# Main_Shield.net
KiCad netlist of a schematic drawn in EAGLE
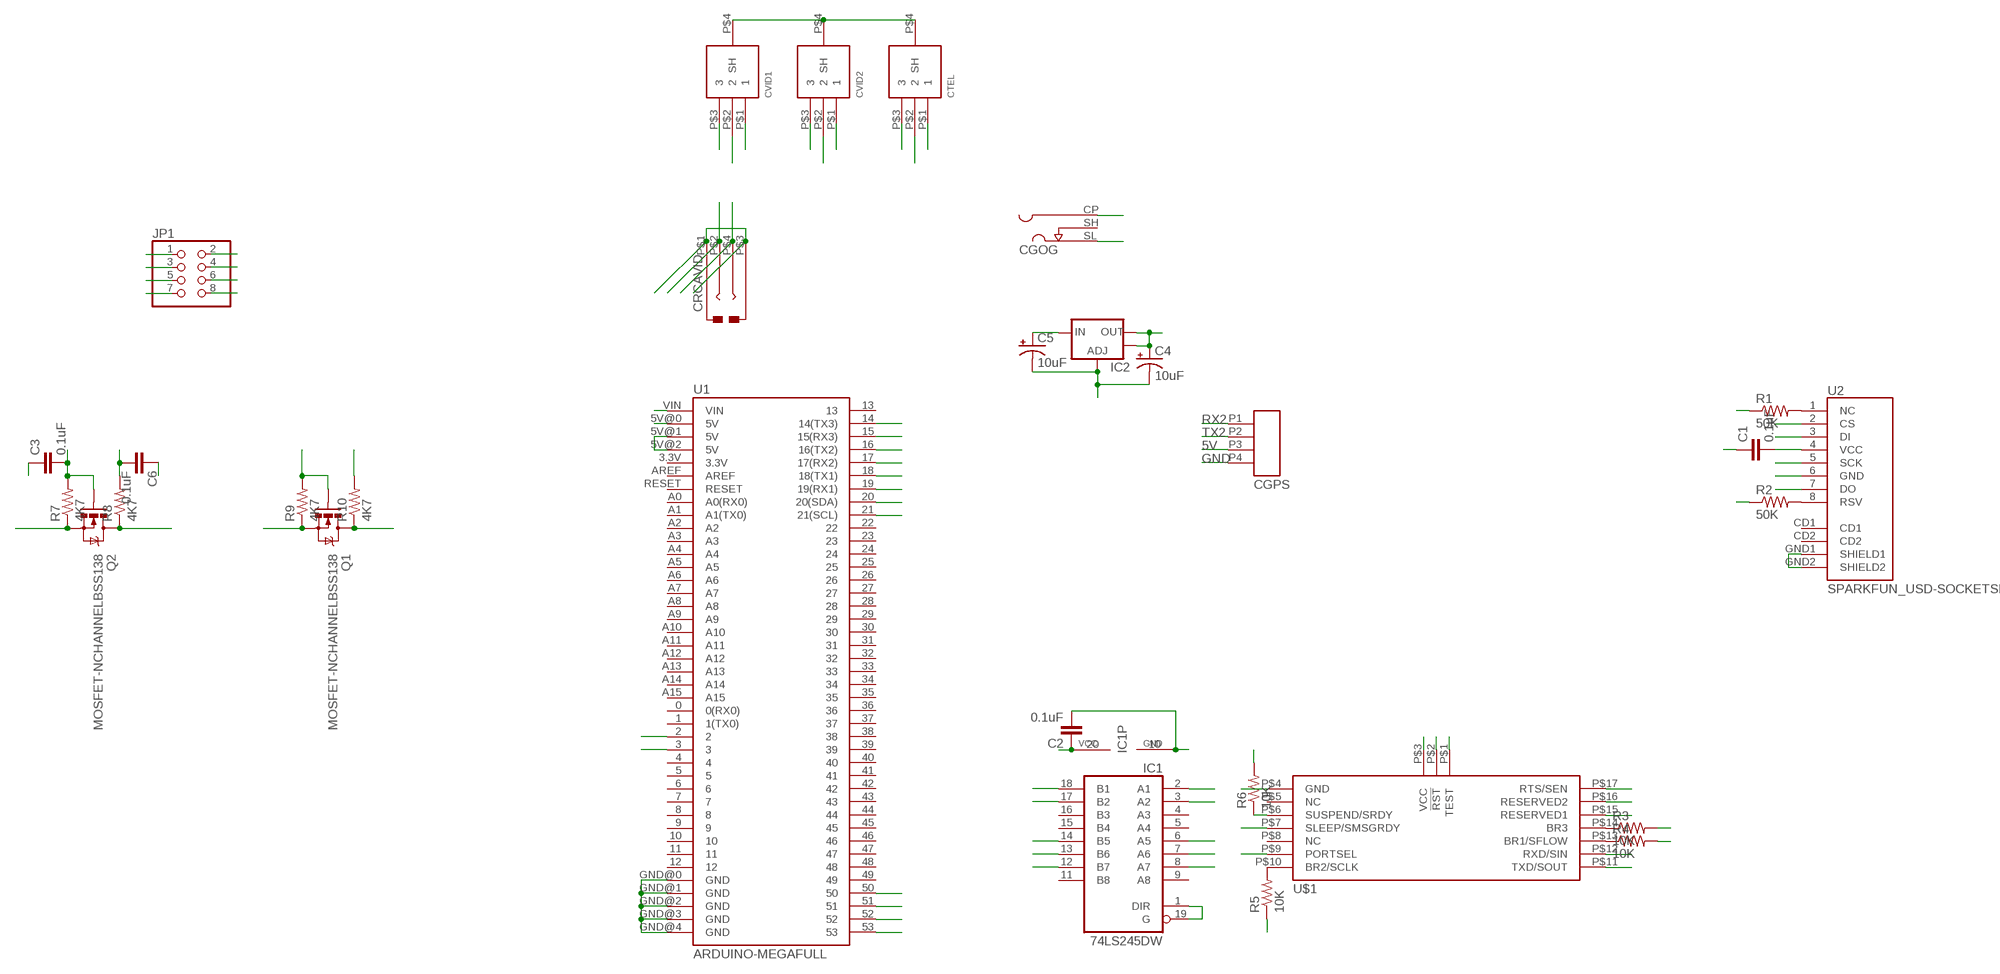
[diagram p0: schematic, sheet 1]

(export (version "E")
  (design (tool "Eeschema 10.0.6"))
  (components
    (comp (ref "C1")
      (value "0.1uF")
      (footprint "eagle-import:0603-CAP")
      (libsource (lib "eagle-import") (part "0.1UF-25V(+80/-20%)(0603)"))
    )
    (comp (ref "C2")
      (value "0.1uF")
      (footprint "eagle-import:0603-CAP")
      (fields (field (name "PROD_ID") "CAP-00810"))
      (libsource (lib "eagle-import") (part "0.1UF-25V(+80/-20%)(0603)"))
    )
    (comp (ref "C3")
      (value "0.1uF")
      (footprint "eagle-import:0603-CAP")
      (fields (field (name "PROD_ID") "CAP-00810"))
      (libsource (lib "eagle-import") (part "0.1UF-25V(+80/-20%)(0603)"))
    )
    (comp (ref "C4")
      (value "10uF")
      (footprint "eagle-import:EIA3216")
      (libsource (lib "eagle-import") (part "10UF-TANT"))
    )
    (comp (ref "C5")
      (value "10uF")
      (footprint "eagle-import:EIA3216")
      (fields (field (name "PROD_ID") "CAP-00811"))
      (libsource (lib "eagle-import") (part "10UF-TANT"))
    )
    (comp (ref "C6")
      (value "0.1uF")
      (footprint "eagle-import:0603-CAP")
      (fields (field (name "PROD_ID") "CAP-00810"))
      (libsource (lib "eagle-import") (part "0.1UF-25V(+80/-20%)(0603)"))
    )
    (comp (ref "CGOG")
      (value "L722RAS")
      (footprint "eagle-import:L722RAS")
      (libsource (lib "eagle-import") (part "L722RAS"))
    )
    (comp (ref "CGPS")
      (value "TRAPC4MSX")
      (footprint "eagle-import:TRAPC4MSX")
      (libsource (lib "eagle-import") (part "TRAPC4MSX"))
    )
    (comp (ref "CRCAVID")
      (value "RCJ-2123")
      (footprint "eagle-import:RCJ-2123")
      (libsource (lib "eagle-import") (part "RCJ-2123"))
    )
    (comp (ref "CTEL")
      (value "TRA3M")
      (footprint "eagle-import:TRA3M")
      (libsource (lib "eagle-import") (part "TRA3M"))
    )
    (comp (ref "CVID1")
      (value "TRA3M")
      (footprint "eagle-import:TRA3M")
      (libsource (lib "eagle-import") (part "TRA3M"))
    )
    (comp (ref "CVID2")
      (value "TRA3M")
      (footprint "eagle-import:TRA3M")
      (libsource (lib "eagle-import") (part "TRA3M"))
    )
    (comp (ref "IC1")
      (value "74LS245DW")
      (footprint "eagle-import:SO20W")
      (libsource (lib "eagle-import") (part "74245DWLS"))
    )
    (comp (ref "IC2")
      (value "V_REG_LM1117SOT223")
      (footprint "eagle-import:SOT223")
      (libsource (lib "eagle-import") (part "V_REG_LM1117SOT223"))
    )
    (comp (ref "JP1")
      (value "PINHD-2X04_MICROMATCH")
      (footprint "eagle-import:MICROMATCH-8")
      (libsource (lib "eagle-import") (part "PINHD-2X04_MICROMATCH"))
    )
    (comp (ref "Q1")
      (value "MOSFET-NCHANNELBSS138")
      (footprint "eagle-import:SOT23")
      (libsource (lib "eagle-import") (part "MOSFET-NCHANNELBSS138"))
    )
    (comp (ref "Q2")
      (value "MOSFET-NCHANNELBSS138")
      (footprint "eagle-import:SOT23")
      (libsource (lib "eagle-import") (part "MOSFET-NCHANNELBSS138"))
    )
    (comp (ref "R1")
      (value "50K")
      (footprint "eagle-import:0603-RES")
      (libsource (lib "eagle-import") (part "RESISTOR0603-RES"))
    )
    (comp (ref "R2")
      (value "50K")
      (footprint "eagle-import:0603-RES")
      (libsource (lib "eagle-import") (part "RESISTOR0603-RES"))
    )
    (comp (ref "R3")
      (value "10K")
      (footprint "eagle-import:0603-RES")
      (libsource (lib "eagle-import") (part "RESISTOR0603-RES"))
    )
    (comp (ref "R4")
      (value "10K")
      (footprint "eagle-import:0603-RES")
      (libsource (lib "eagle-import") (part "RESISTOR0603-RES"))
    )
    (comp (ref "R5")
      (value "10K")
      (footprint "eagle-import:0603-RES")
      (libsource (lib "eagle-import") (part "RESISTOR0603-RES"))
    )
    (comp (ref "R6")
      (value "10K")
      (footprint "eagle-import:0603-RES")
      (libsource (lib "eagle-import") (part "RESISTOR0603-RES"))
    )
    (comp (ref "R7")
      (value "4K7")
      (footprint "eagle-import:0603-RES")
      (libsource (lib "eagle-import") (part "RESISTOR0603-RES"))
    )
    (comp (ref "R8")
      (value "4K7")
      (footprint "eagle-import:0603-RES")
      (libsource (lib "eagle-import") (part "RESISTOR0603-RES"))
    )
    (comp (ref "R9")
      (value "4K7")
      (footprint "eagle-import:0603-RES")
      (libsource (lib "eagle-import") (part "RESISTOR0603-RES"))
    )
    (comp (ref "R10")
      (value "4K7")
      (footprint "eagle-import:0603-RES")
      (libsource (lib "eagle-import") (part "RESISTOR0603-RES"))
    )
    (comp (ref "U$1")
      (value "ANTAP281MXIB")
      (footprint "eagle-import:ANTAP281MXIB")
      (libsource (lib "eagle-import") (part "ANTAP281MXIB"))
    )
    (comp (ref "U1")
      (value "ARDUINO-MEGAFULL")
      (footprint "eagle-import:ARDUINO_MEGA")
      (libsource (lib "eagle-import") (part "ARDUINO-MEGAFULL"))
    )
    (comp (ref "U2")
      (value "SPARKFUN_USD-SOCKETSMD")
      (footprint "eagle-import:SPARKFUN_MICRO-SD-SOCKET-PP")
      (libsource (lib "eagle-import") (part "SPARKFUN_USD-SOCKETSMD"))
    )
  )
  (nets
    (net (code "1") (name "/3V3") (class "Default")
      (node (ref "C1") (pin "2") (pinfunction "2_2") (pintype "passive"))
      (node (ref "C2") (pin "1") (pinfunction "1_1") (pintype "passive"))
      (node (ref "C3") (pin "2") (pinfunction "2_2") (pintype "passive"))
      (node (ref "C4") (pin "A") (pinfunction "+_A") (pintype "passive"))
      (node (ref "IC1") (pin "20") (pinfunction "VCC_20") (pintype "power_in"))
      (node (ref "IC2") (pin "2") (pinfunction "OUT_2") (pintype "output"))
      (node (ref "IC2") (pin "4") (pinfunction "OUT_4") (pintype "output"))
      (node (ref "JP1") (pin "2") (pinfunction "2_2") (pintype "passive"))
      (node (ref "Q1") (pin "1") (pinfunction "G_1") (pintype "passive"))
      (node (ref "Q2") (pin "1") (pinfunction "G_1") (pintype "passive"))
      (node (ref "R1") (pin "1") (pinfunction "1_1") (pintype "passive"))
      (node (ref "R2") (pin "1") (pinfunction "1_1") (pintype "passive"))
      (node (ref "R3") (pin "2") (pinfunction "2_2") (pintype "passive"))
      (node (ref "R4") (pin "2") (pinfunction "2_2") (pintype "passive"))
      (node (ref "R5") (pin "1") (pinfunction "1_1") (pintype "passive"))
      (node (ref "R6") (pin "2") (pinfunction "2_2") (pintype "passive"))
      (node (ref "R7") (pin "2") (pinfunction "2_2") (pintype "passive"))
      (node (ref "R9") (pin "2") (pinfunction "2_2") (pintype "passive"))
      (node (ref "U$1") (pin "P$3") (pinfunction "VCC_P$3") (pintype "bidirectional"))
      (node (ref "U2") (pin "4") (pinfunction "VCC_4") (pintype "bidirectional"))
    )
    (net (code "2") (name "/5V") (class "Default")
      (node (ref "C5") (pin "A") (pinfunction "+_A") (pintype "passive"))
      (node (ref "C6") (pin "2") (pinfunction "2_2") (pintype "passive"))
      (node (ref "CGPS") (pin "P3") (pinfunction "P$3_P3") (pintype "bidirectional"))
      (node (ref "CVID1") (pin "P$1") (pinfunction "1_P$1") (pintype "bidirectional"))
      (node (ref "CVID2") (pin "P$1") (pinfunction "1_P$1") (pintype "bidirectional"))
      (node (ref "IC2") (pin "3") (pinfunction "IN_3") (pintype "input"))
      (node (ref "JP1") (pin "4") (pinfunction "4_4") (pintype "passive"))
      (node (ref "R10") (pin "2") (pinfunction "2_2") (pintype "passive"))
      (node (ref "R8") (pin "2") (pinfunction "2_2") (pintype "passive"))
      (node (ref "U1") (pin "5V@0") (pinfunction "5V_5V@0") (pintype "bidirectional"))
      (node (ref "U1") (pin "5V@1") (pinfunction "5V_5V@1") (pintype "bidirectional"))
      (node (ref "U1") (pin "5V@2") (pinfunction "5V_5V@2") (pintype "bidirectional"))
    )
    (net (code "3") (name "/CSMMC") (class "Default")
      (node (ref "IC1") (pin "8") (pinfunction "A7_8") (pintype "bidirectional"))
      (node (ref "U2") (pin "2") (pinfunction "CS_2") (pintype "bidirectional"))
    )
    (net (code "4") (name "/DIMMC") (class "Default")
      (node (ref "IC1") (pin "7") (pinfunction "A6_7") (pintype "bidirectional"))
      (node (ref "U2") (pin "3") (pinfunction "DI_3") (pintype "bidirectional"))
    )
    (net (code "5") (name "/DOMMC") (class "Default")
      (node (ref "U1") (pin "50") (pinfunction "50_50") (pintype "bidirectional"))
      (node (ref "U2") (pin "7") (pinfunction "DO_7") (pintype "bidirectional"))
    )
    (net (code "6") (name "/GND") (class "Default")
      (node (ref "C1") (pin "1") (pinfunction "1_1") (pintype "passive"))
      (node (ref "C2") (pin "2") (pinfunction "2_2") (pintype "passive"))
      (node (ref "C3") (pin "1") (pinfunction "1_1") (pintype "passive"))
      (node (ref "C4") (pin "C") (pinfunction "-_C") (pintype "passive"))
      (node (ref "C5") (pin "C") (pinfunction "-_C") (pintype "passive"))
      (node (ref "C6") (pin "1") (pinfunction "1_1") (pintype "passive"))
      (node (ref "CGOG") (pin "SL") (pinfunction "SLEEVE_SL") (pintype "bidirectional"))
      (node (ref "CGPS") (pin "P4") (pinfunction "P$4_P4") (pintype "bidirectional"))
      (node (ref "CRCAVID") (pin "P$1") (pinfunction "P$1_P$1") (pintype "bidirectional"))
      (node (ref "CRCAVID") (pin "P$3") (pinfunction "P$3_P$3") (pintype "bidirectional"))
      (node (ref "CTEL") (pin "P$3") (pinfunction "3_P$3") (pintype "bidirectional"))
      (node (ref "CTEL") (pin "P$4") (pinfunction "SH_P$4") (pintype "bidirectional"))
      (node (ref "CVID1") (pin "P$3") (pinfunction "3_P$3") (pintype "bidirectional"))
      (node (ref "CVID1") (pin "P$4") (pinfunction "SH_P$4") (pintype "bidirectional"))
      (node (ref "CVID2") (pin "P$3") (pinfunction "3_P$3") (pintype "bidirectional"))
      (node (ref "CVID2") (pin "P$4") (pinfunction "SH_P$4") (pintype "bidirectional"))
      (node (ref "IC1") (pin "1") (pinfunction "DIR_1") (pintype "input"))
      (node (ref "IC1") (pin "10") (pinfunction "GND_10") (pintype "power_in"))
      (node (ref "IC1") (pin "19") (pinfunction "G_19") (pintype "input"))
      (node (ref "IC2") (pin "1") (pinfunction "ADJ_1") (pintype "input"))
      (node (ref "JP1") (pin "1") (pinfunction "1_1") (pintype "passive"))
      (node (ref "JP1") (pin "3") (pinfunction "3_3") (pintype "passive"))
      (node (ref "U$1") (pin "P$1") (pinfunction "TEST_P$1") (pintype "bidirectional"))
      (node (ref "U$1") (pin "P$15") (pinfunction "RESERVED1_P$15") (pintype "bidirectional"))
      (node (ref "U$1") (pin "P$16") (pinfunction "RESERVED2_P$16") (pintype "bidirectional"))
      (node (ref "U$1") (pin "P$4") (pinfunction "GND_P$4") (pintype "bidirectional"))
      (node (ref "U$1") (pin "P$7") (pinfunction "SLEEP/SMSGRDY_P$7") (pintype "bidirectional"))
      (node (ref "U$1") (pin "P$9") (pinfunction "PORTSEL_P$9") (pintype "bidirectional"))
      (node (ref "U1") (pin "GND@0") (pinfunction "GND_GND@0") (pintype "bidirectional"))
      (node (ref "U1") (pin "GND@1") (pinfunction "GND_GND@1") (pintype "bidirectional"))
      (node (ref "U1") (pin "GND@2") (pinfunction "GND_GND@2") (pintype "bidirectional"))
      (node (ref "U1") (pin "GND@3") (pinfunction "GND_GND@3") (pintype "bidirectional"))
      (node (ref "U1") (pin "GND@4") (pinfunction "GND_GND@4") (pintype "bidirectional"))
      (node (ref "U2") (pin "6") (pinfunction "GND_6") (pintype "bidirectional"))
      (node (ref "U2") (pin "GND1") (pinfunction "SHIELD1_GND1") (pintype "bidirectional"))
      (node (ref "U2") (pin "GND2") (pinfunction "SHIELD2_GND2") (pintype "bidirectional"))
    )
    (net (code "7") (name "/MOSI") (class "Default")
      (node (ref "IC1") (pin "13") (pinfunction "B6_13") (pintype "bidirectional"))
      (node (ref "U1") (pin "51") (pinfunction "51_51") (pintype "bidirectional"))
    )
    (net (code "8") (name "/RTSANT") (class "Default")
      (node (ref "U$1") (pin "P$17") (pinfunction "RTS/SEN_P$17") (pintype "bidirectional"))
      (node (ref "U1") (pin "2") (pinfunction "2_2") (pintype "bidirectional"))
    )
    (net (code "9") (name "/RX2") (class "Default")
      (node (ref "CGPS") (pin "P1") (pinfunction "P$1_P1") (pintype "bidirectional"))
      (node (ref "U1") (pin "17") (pinfunction "17(RX2)_17") (pintype "bidirectional"))
    )
    (net (code "10") (name "/RXANT") (class "Default")
      (node (ref "IC1") (pin "2") (pinfunction "A1_2") (pintype "bidirectional"))
      (node (ref "U$1") (pin "P$12") (pinfunction "RXD/SIN_P$12") (pintype "bidirectional"))
    )
    (net (code "11") (name "/RXOSD") (class "Default")
      (node (ref "CTEL") (pin "P$2") (pinfunction "2_P$2") (pintype "bidirectional"))
      (node (ref "U1") (pin "14") (pinfunction "14(TX3)_14") (pintype "bidirectional"))
    )
    (net (code "12") (name "/SCK") (class "Default")
      (node (ref "IC1") (pin "14") (pinfunction "B5_14") (pintype "bidirectional"))
      (node (ref "U1") (pin "52") (pinfunction "52_52") (pintype "bidirectional"))
    )
    (net (code "13") (name "/SCKMMC") (class "Default")
      (node (ref "IC1") (pin "6") (pinfunction "A5_6") (pintype "bidirectional"))
      (node (ref "U2") (pin "5") (pinfunction "SCK_5") (pintype "bidirectional"))
    )
    (net (code "14") (name "/SCL3V3") (class "Default")
      (node (ref "JP1") (pin "7") (pinfunction "7_7") (pintype "passive"))
      (node (ref "Q1") (pin "2") (pinfunction "S_2") (pintype "passive"))
      (node (ref "R9") (pin "1") (pinfunction "1_1") (pintype "passive"))
    )
    (net (code "15") (name "/SCL5V") (class "Default")
      (node (ref "JP1") (pin "8") (pinfunction "8_8") (pintype "passive"))
      (node (ref "Q1") (pin "3") (pinfunction "D_3") (pintype "passive"))
      (node (ref "R10") (pin "1") (pinfunction "1_1") (pintype "passive"))
      (node (ref "U1") (pin "21") (pinfunction "21(SCL)_21") (pintype "bidirectional"))
    )
    (net (code "16") (name "/SDA3V3") (class "Default")
      (node (ref "JP1") (pin "5") (pinfunction "5_5") (pintype "passive"))
      (node (ref "Q2") (pin "2") (pinfunction "S_2") (pintype "passive"))
      (node (ref "R7") (pin "1") (pinfunction "1_1") (pintype "passive"))
    )
    (net (code "17") (name "/SDA5V") (class "Default")
      (node (ref "JP1") (pin "6") (pinfunction "6_6") (pintype "passive"))
      (node (ref "Q2") (pin "3") (pinfunction "D_3") (pintype "passive"))
      (node (ref "R8") (pin "1") (pinfunction "1_1") (pintype "passive"))
      (node (ref "U1") (pin "20") (pinfunction "20(SDA)_20") (pintype "bidirectional"))
    )
    (net (code "18") (name "/SS") (class "Default")
      (node (ref "IC1") (pin "12") (pinfunction "B7_12") (pintype "bidirectional"))
      (node (ref "U1") (pin "53") (pinfunction "53_53") (pintype "bidirectional"))
    )
    (net (code "19") (name "/TX1") (class "Default")
      (node (ref "IC1") (pin "18") (pinfunction "B1_18") (pintype "bidirectional"))
      (node (ref "U1") (pin "18") (pinfunction "18(TX1)_18") (pintype "bidirectional"))
    )
    (net (code "20") (name "/TX2") (class "Default")
      (node (ref "CGPS") (pin "P2") (pinfunction "P$2_P2") (pintype "bidirectional"))
      (node (ref "U1") (pin "16") (pinfunction "16(TX2)_16") (pintype "bidirectional"))
    )
    (net (code "21") (name "/TXANT") (class "Default")
      (node (ref "U$1") (pin "P$11") (pinfunction "TXD/SOUT_P$11") (pintype "bidirectional"))
      (node (ref "U1") (pin "19") (pinfunction "19(RX1)_19") (pintype "bidirectional"))
    )
    (net (code "22") (name "/TXOSD") (class "Default")
      (node (ref "CTEL") (pin "P$1") (pinfunction "1_P$1") (pintype "bidirectional"))
      (node (ref "U1") (pin "15") (pinfunction "15(RX3)_15") (pintype "bidirectional"))
    )
    (net (code "23") (name "/VBAT") (class "Default")
      (node (ref "CGOG") (pin "CP") (pinfunction "CENTRE_CP") (pintype "bidirectional"))
      (node (ref "U1") (pin "VIN") (pinfunction "VIN_VIN") (pintype "bidirectional"))
    )
    (net (code "24") (name "/VID1") (class "Default")
      (node (ref "CRCAVID") (pin "P$2") (pinfunction "P$2_P$2") (pintype "bidirectional"))
      (node (ref "CVID1") (pin "P$2") (pinfunction "2_P$2") (pintype "bidirectional"))
    )
    (net (code "25") (name "/VID2") (class "Default")
      (node (ref "CRCAVID") (pin "P$4") (pinfunction "P$4_P$4") (pintype "bidirectional"))
      (node (ref "CVID2") (pin "P$2") (pinfunction "2_P$2") (pintype "bidirectional"))
    )
    (net (code "26") (name "/~{RST}ANT") (class "Default")
      (node (ref "IC1") (pin "3") (pinfunction "A2_3") (pintype "bidirectional"))
      (node (ref "U$1") (pin "P$2") (pinfunction "~{RST}_P$2") (pintype "bidirectional"))
    )
    (net (code "27") (name "/~{RST}ANT5V") (class "Default")
      (node (ref "IC1") (pin "17") (pinfunction "B2_17") (pintype "bidirectional"))
      (node (ref "U1") (pin "3") (pinfunction "3_3") (pintype "bidirectional"))
    )
    (net (code "28") (name "Net-(U$1-BR1{slash}SFLOW)") (class "Default")
      (node (ref "R4") (pin "1") (pinfunction "1_1") (pintype "passive"))
      (node (ref "U$1") (pin "P$13") (pinfunction "BR1/SFLOW_P$13") (pintype "bidirectional"))
    )
    (net (code "29") (name "Net-(U$1-BR2{slash}SCLK)") (class "Default")
      (node (ref "R5") (pin "2") (pinfunction "2_2") (pintype "passive"))
      (node (ref "U$1") (pin "P$10") (pinfunction "BR2/SCLK_P$10") (pintype "bidirectional"))
    )
    (net (code "30") (name "Net-(U$1-BR3)") (class "Default")
      (node (ref "R3") (pin "1") (pinfunction "1_1") (pintype "passive"))
      (node (ref "U$1") (pin "P$14") (pinfunction "BR3_P$14") (pintype "bidirectional"))
    )
    (net (code "31") (name "Net-(U$1-SUSPEND{slash}SRDY)") (class "Default")
      (node (ref "R6") (pin "1") (pinfunction "1_1") (pintype "passive"))
      (node (ref "U$1") (pin "P$6") (pinfunction "SUSPEND/SRDY_P$6") (pintype "bidirectional"))
    )
    (net (code "32") (name "Net-(U2-NC)") (class "Default")
      (node (ref "R1") (pin "2") (pinfunction "2_2") (pintype "passive"))
      (node (ref "U2") (pin "1") (pinfunction "NC_1") (pintype "bidirectional"))
    )
    (net (code "33") (name "Net-(U2-RSV)") (class "Default")
      (node (ref "R2") (pin "2") (pinfunction "2_2") (pintype "passive"))
      (node (ref "U2") (pin "8") (pinfunction "RSV_8") (pintype "bidirectional"))
    )
    (net (code "34") (name "unconnected-(CGOG-SHUNT-PadSH)") (class "Default")
      (node (ref "CGOG") (pin "SH") (pinfunction "SHUNT_SH") (pintype "bidirectional"))
    )
    (net (code "35") (name "unconnected-(IC1A-A3-Pad4)") (class "Default")
      (node (ref "IC1") (pin "4") (pinfunction "A3_4") (pintype "bidirectional"))
    )
    (net (code "36") (name "unconnected-(IC1A-A4-Pad5)") (class "Default")
      (node (ref "IC1") (pin "5") (pinfunction "A4_5") (pintype "bidirectional"))
    )
    (net (code "37") (name "unconnected-(IC1A-A8-Pad9)") (class "Default")
      (node (ref "IC1") (pin "9") (pinfunction "A8_9") (pintype "bidirectional"))
    )
    (net (code "38") (name "unconnected-(IC1A-B3-Pad16)") (class "Default")
      (node (ref "IC1") (pin "16") (pinfunction "B3_16") (pintype "bidirectional"))
    )
    (net (code "39") (name "unconnected-(IC1A-B4-Pad15)") (class "Default")
      (node (ref "IC1") (pin "15") (pinfunction "B4_15") (pintype "bidirectional"))
    )
    (net (code "40") (name "unconnected-(IC1A-B8-Pad11)") (class "Default")
      (node (ref "IC1") (pin "11") (pinfunction "B8_11") (pintype "bidirectional"))
    )
    (net (code "41") (name "unconnected-(U$1-NC-PadP$5)") (class "Default")
      (node (ref "U$1") (pin "P$5") (pinfunction "NC_P$5") (pintype "bidirectional"))
    )
    (net (code "42") (name "unconnected-(U$1-NC-PadP$8)") (class "Default")
      (node (ref "U$1") (pin "P$8") (pinfunction "NC_P$8") (pintype "bidirectional"))
    )
    (net (code "43") (name "unconnected-(U1-0(RX0)-Pad0)") (class "Default")
      (node (ref "U1") (pin "0") (pinfunction "0(RX0)_0") (pintype "bidirectional"))
    )
    (net (code "44") (name "unconnected-(U1-1(TX0)-Pad1)") (class "Default")
      (node (ref "U1") (pin "1") (pinfunction "1(TX0)_1") (pintype "bidirectional"))
    )
    (net (code "45") (name "unconnected-(U1-A0(RX0)-PadA0)") (class "Default")
      (node (ref "U1") (pin "A0") (pinfunction "A0(RX0)_A0") (pintype "bidirectional"))
    )
    (net (code "46") (name "unconnected-(U1-A1(TX0)-PadA1)") (class "Default")
      (node (ref "U1") (pin "A1") (pinfunction "A1(TX0)_A1") (pintype "bidirectional"))
    )
    (net (code "47") (name "unconnected-(U1-Pad3.3V)") (class "Default")
      (node (ref "U1") (pin "3.3V") (pinfunction "3.3V_3.3V") (pintype "bidirectional"))
    )
    (net (code "48") (name "unconnected-(U1-Pad4)") (class "Default")
      (node (ref "U1") (pin "4") (pinfunction "4_4") (pintype "bidirectional"))
    )
    (net (code "49") (name "unconnected-(U1-Pad5)") (class "Default")
      (node (ref "U1") (pin "5") (pinfunction "5_5") (pintype "bidirectional"))
    )
    (net (code "50") (name "unconnected-(U1-Pad6)") (class "Default")
      (node (ref "U1") (pin "6") (pinfunction "6_6") (pintype "bidirectional"))
    )
    (net (code "51") (name "unconnected-(U1-Pad7)") (class "Default")
      (node (ref "U1") (pin "7") (pinfunction "7_7") (pintype "bidirectional"))
    )
    (net (code "52") (name "unconnected-(U1-Pad8)") (class "Default")
      (node (ref "U1") (pin "8") (pinfunction "8_8") (pintype "bidirectional"))
    )
    (net (code "53") (name "unconnected-(U1-Pad9)") (class "Default")
      (node (ref "U1") (pin "9") (pinfunction "9_9") (pintype "bidirectional"))
    )
    (net (code "54") (name "unconnected-(U1-Pad10)") (class "Default")
      (node (ref "U1") (pin "10") (pinfunction "10_10") (pintype "bidirectional"))
    )
    (net (code "55") (name "unconnected-(U1-Pad11)") (class "Default")
      (node (ref "U1") (pin "11") (pinfunction "11_11") (pintype "bidirectional"))
    )
    (net (code "56") (name "unconnected-(U1-Pad12)") (class "Default")
      (node (ref "U1") (pin "12") (pinfunction "12_12") (pintype "bidirectional"))
    )
    (net (code "57") (name "unconnected-(U1-Pad13)") (class "Default")
      (node (ref "U1") (pin "13") (pinfunction "13_13") (pintype "bidirectional"))
    )
    (net (code "58") (name "unconnected-(U1-Pad22)") (class "Default")
      (node (ref "U1") (pin "22") (pinfunction "22_22") (pintype "bidirectional"))
    )
    (net (code "59") (name "unconnected-(U1-Pad23)") (class "Default")
      (node (ref "U1") (pin "23") (pinfunction "23_23") (pintype "bidirectional"))
    )
    (net (code "60") (name "unconnected-(U1-Pad24)") (class "Default")
      (node (ref "U1") (pin "24") (pinfunction "24_24") (pintype "bidirectional"))
    )
    (net (code "61") (name "unconnected-(U1-Pad25)") (class "Default")
      (node (ref "U1") (pin "25") (pinfunction "25_25") (pintype "bidirectional"))
    )
    (net (code "62") (name "unconnected-(U1-Pad26)") (class "Default")
      (node (ref "U1") (pin "26") (pinfunction "26_26") (pintype "bidirectional"))
    )
    (net (code "63") (name "unconnected-(U1-Pad27)") (class "Default")
      (node (ref "U1") (pin "27") (pinfunction "27_27") (pintype "bidirectional"))
    )
    (net (code "64") (name "unconnected-(U1-Pad28)") (class "Default")
      (node (ref "U1") (pin "28") (pinfunction "28_28") (pintype "bidirectional"))
    )
    (net (code "65") (name "unconnected-(U1-Pad29)") (class "Default")
      (node (ref "U1") (pin "29") (pinfunction "29_29") (pintype "bidirectional"))
    )
    (net (code "66") (name "unconnected-(U1-Pad30)") (class "Default")
      (node (ref "U1") (pin "30") (pinfunction "30_30") (pintype "bidirectional"))
    )
    (net (code "67") (name "unconnected-(U1-Pad31)") (class "Default")
      (node (ref "U1") (pin "31") (pinfunction "31_31") (pintype "bidirectional"))
    )
    (net (code "68") (name "unconnected-(U1-Pad32)") (class "Default")
      (node (ref "U1") (pin "32") (pinfunction "32_32") (pintype "bidirectional"))
    )
    (net (code "69") (name "unconnected-(U1-Pad33)") (class "Default")
      (node (ref "U1") (pin "33") (pinfunction "33_33") (pintype "bidirectional"))
    )
    (net (code "70") (name "unconnected-(U1-Pad34)") (class "Default")
      (node (ref "U1") (pin "34") (pinfunction "34_34") (pintype "bidirectional"))
    )
    (net (code "71") (name "unconnected-(U1-Pad35)") (class "Default")
      (node (ref "U1") (pin "35") (pinfunction "35_35") (pintype "bidirectional"))
    )
    (net (code "72") (name "unconnected-(U1-Pad36)") (class "Default")
      (node (ref "U1") (pin "36") (pinfunction "36_36") (pintype "bidirectional"))
    )
    (net (code "73") (name "unconnected-(U1-Pad37)") (class "Default")
      (node (ref "U1") (pin "37") (pinfunction "37_37") (pintype "bidirectional"))
    )
    (net (code "74") (name "unconnected-(U1-Pad38)") (class "Default")
      (node (ref "U1") (pin "38") (pinfunction "38_38") (pintype "bidirectional"))
    )
    (net (code "75") (name "unconnected-(U1-Pad39)") (class "Default")
      (node (ref "U1") (pin "39") (pinfunction "39_39") (pintype "bidirectional"))
    )
    (net (code "76") (name "unconnected-(U1-Pad40)") (class "Default")
      (node (ref "U1") (pin "40") (pinfunction "40_40") (pintype "bidirectional"))
    )
    (net (code "77") (name "unconnected-(U1-Pad41)") (class "Default")
      (node (ref "U1") (pin "41") (pinfunction "41_41") (pintype "bidirectional"))
    )
    (net (code "78") (name "unconnected-(U1-Pad42)") (class "Default")
      (node (ref "U1") (pin "42") (pinfunction "42_42") (pintype "bidirectional"))
    )
    (net (code "79") (name "unconnected-(U1-Pad43)") (class "Default")
      (node (ref "U1") (pin "43") (pinfunction "43_43") (pintype "bidirectional"))
    )
    (net (code "80") (name "unconnected-(U1-Pad44)") (class "Default")
      (node (ref "U1") (pin "44") (pinfunction "44_44") (pintype "bidirectional"))
    )
    (net (code "81") (name "unconnected-(U1-Pad45)") (class "Default")
      (node (ref "U1") (pin "45") (pinfunction "45_45") (pintype "bidirectional"))
    )
    (net (code "82") (name "unconnected-(U1-Pad46)") (class "Default")
      (node (ref "U1") (pin "46") (pinfunction "46_46") (pintype "bidirectional"))
    )
    (net (code "83") (name "unconnected-(U1-Pad47)") (class "Default")
      (node (ref "U1") (pin "47") (pinfunction "47_47") (pintype "bidirectional"))
    )
    (net (code "84") (name "unconnected-(U1-Pad48)") (class "Default")
      (node (ref "U1") (pin "48") (pinfunction "48_48") (pintype "bidirectional"))
    )
    (net (code "85") (name "unconnected-(U1-Pad49)") (class "Default")
      (node (ref "U1") (pin "49") (pinfunction "49_49") (pintype "bidirectional"))
    )
    (net (code "86") (name "unconnected-(U1-PadA2)") (class "Default")
      (node (ref "U1") (pin "A2") (pinfunction "A2_A2") (pintype "bidirectional"))
    )
    (net (code "87") (name "unconnected-(U1-PadA3)") (class "Default")
      (node (ref "U1") (pin "A3") (pinfunction "A3_A3") (pintype "bidirectional"))
    )
    (net (code "88") (name "unconnected-(U1-PadA4)") (class "Default")
      (node (ref "U1") (pin "A4") (pinfunction "A4_A4") (pintype "bidirectional"))
    )
    (net (code "89") (name "unconnected-(U1-PadA5)") (class "Default")
      (node (ref "U1") (pin "A5") (pinfunction "A5_A5") (pintype "bidirectional"))
    )
    (net (code "90") (name "unconnected-(U1-PadA6)") (class "Default")
      (node (ref "U1") (pin "A6") (pinfunction "A6_A6") (pintype "bidirectional"))
    )
    (net (code "91") (name "unconnected-(U1-PadA7)") (class "Default")
      (node (ref "U1") (pin "A7") (pinfunction "A7_A7") (pintype "bidirectional"))
    )
    (net (code "92") (name "unconnected-(U1-PadA8)") (class "Default")
      (node (ref "U1") (pin "A8") (pinfunction "A8_A8") (pintype "bidirectional"))
    )
    (net (code "93") (name "unconnected-(U1-PadA9)") (class "Default")
      (node (ref "U1") (pin "A9") (pinfunction "A9_A9") (pintype "bidirectional"))
    )
    (net (code "94") (name "unconnected-(U1-PadA10)") (class "Default")
      (node (ref "U1") (pin "A10") (pinfunction "A10_A10") (pintype "bidirectional"))
    )
    (net (code "95") (name "unconnected-(U1-PadA11)") (class "Default")
      (node (ref "U1") (pin "A11") (pinfunction "A11_A11") (pintype "bidirectional"))
    )
    (net (code "96") (name "unconnected-(U1-PadA12)") (class "Default")
      (node (ref "U1") (pin "A12") (pinfunction "A12_A12") (pintype "bidirectional"))
    )
    (net (code "97") (name "unconnected-(U1-PadA13)") (class "Default")
      (node (ref "U1") (pin "A13") (pinfunction "A13_A13") (pintype "bidirectional"))
    )
    (net (code "98") (name "unconnected-(U1-PadA14)") (class "Default")
      (node (ref "U1") (pin "A14") (pinfunction "A14_A14") (pintype "bidirectional"))
    )
    (net (code "99") (name "unconnected-(U1-PadA15)") (class "Default")
      (node (ref "U1") (pin "A15") (pinfunction "A15_A15") (pintype "bidirectional"))
    )
    (net (code "100") (name "unconnected-(U1-PadAREF)") (class "Default")
      (node (ref "U1") (pin "AREF") (pinfunction "AREF_AREF") (pintype "bidirectional"))
    )
    (net (code "101") (name "unconnected-(U1-PadRESET)") (class "Default")
      (node (ref "U1") (pin "RESET") (pinfunction "RESET_RESET") (pintype "bidirectional"))
    )
    (net (code "102") (name "unconnected-(U2-PadCD1)") (class "Default")
      (node (ref "U2") (pin "CD1") (pinfunction "CD1_CD1") (pintype "bidirectional"))
    )
    (net (code "103") (name "unconnected-(U2-PadCD2)") (class "Default")
      (node (ref "U2") (pin "CD2") (pinfunction "CD2_CD2") (pintype "bidirectional"))
    )
  )
)
